# Clock_Flash.net
KiCad netlist of a schematic drawn in Altium Designer
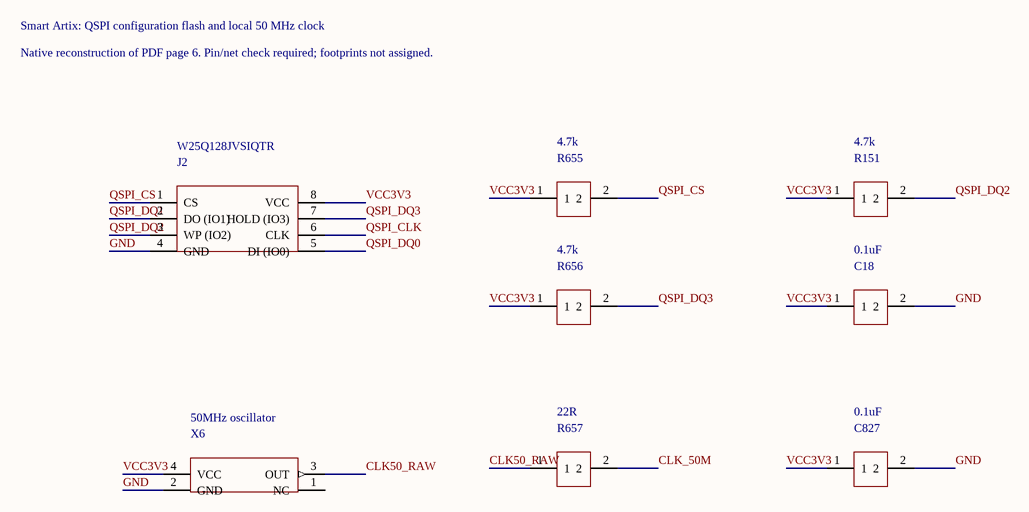
[diagram p0: Clock_Flash.SchDoc]

(export (version "E")
  (design (tool "Eeschema 10.0.6"))
  (components
    (comp (ref "C18")
      (value "0.1uF")
      (description "Reconstructed from Smart Artix reference PDF")
      (libsource (lib "*") (part "0.1uF"))
    )
    (comp (ref "C827")
      (value "0.1uF")
      (description "Reconstructed from Smart Artix reference PDF")
      (libsource (lib "*") (part "0.1uF"))
    )
    (comp (ref "J2")
      (value "W25Q128JVSIQTR")
      (description "Reconstructed from Smart Artix reference PDF")
      (libsource (lib "*") (part "W25Q128JVSIQTR"))
    )
    (comp (ref "R151")
      (value "4.7k")
      (description "Reconstructed from Smart Artix reference PDF")
      (libsource (lib "*") (part "4.7k"))
    )
    (comp (ref "R655")
      (value "4.7k")
      (description "Reconstructed from Smart Artix reference PDF")
      (libsource (lib "*") (part "4.7k"))
    )
    (comp (ref "R656")
      (value "4.7k")
      (description "Reconstructed from Smart Artix reference PDF")
      (libsource (lib "*") (part "4.7k"))
    )
    (comp (ref "R657")
      (value "22R")
      (description "Reconstructed from Smart Artix reference PDF")
      (libsource (lib "*") (part "22R"))
    )
    (comp (ref "X6")
      (value "50MHz oscillator")
      (description "Reconstructed from Smart Artix reference PDF")
      (libsource (lib "*") (part "50MHz oscillator"))
    )
  )
  (nets
    (net (code "1") (name "/CLK50_RAW") (class "Default")
      (node (ref "R657") (pin "1") (pinfunction "1_1") (pintype "passive"))
      (node (ref "X6") (pin "3") (pinfunction "OUT_3") (pintype "output"))
    )
    (net (code "2") (name "/CLK_50M") (class "Default")
      (node (ref "R657") (pin "2") (pinfunction "2_2") (pintype "passive"))
    )
    (net (code "3") (name "/GND") (class "Default")
      (node (ref "C18") (pin "2") (pinfunction "2_2") (pintype "passive"))
      (node (ref "C827") (pin "2") (pinfunction "2_2") (pintype "passive"))
      (node (ref "J2") (pin "4") (pinfunction "GND_4") (pintype "power_in"))
      (node (ref "X6") (pin "2") (pinfunction "GND_2") (pintype "power_in"))
    )
    (net (code "4") (name "/QSPI_CLK") (class "Default")
      (node (ref "J2") (pin "6") (pinfunction "CLK_6") (pintype "passive"))
    )
    (net (code "5") (name "/QSPI_CS") (class "Default")
      (node (ref "J2") (pin "1") (pinfunction "CS_1") (pintype "passive"))
      (node (ref "R655") (pin "2") (pinfunction "2_2") (pintype "passive"))
    )
    (net (code "6") (name "/QSPI_DQ0") (class "Default")
      (node (ref "J2") (pin "5") (pinfunction "DI_(IO0)_5") (pintype "passive"))
    )
    (net (code "7") (name "/QSPI_DQ1") (class "Default")
      (node (ref "J2") (pin "2") (pinfunction "DO_(IO1)_2") (pintype "passive"))
    )
    (net (code "8") (name "/QSPI_DQ2") (class "Default")
      (node (ref "J2") (pin "3") (pinfunction "WP_(IO2)_3") (pintype "passive"))
      (node (ref "R151") (pin "2") (pinfunction "2_2") (pintype "passive"))
    )
    (net (code "9") (name "/QSPI_DQ3") (class "Default")
      (node (ref "J2") (pin "7") (pinfunction "HOLD_(IO3)_7") (pintype "passive"))
      (node (ref "R656") (pin "2") (pinfunction "2_2") (pintype "passive"))
    )
    (net (code "10") (name "/VCC3V3") (class "Default")
      (node (ref "C18") (pin "1") (pinfunction "1_1") (pintype "passive"))
      (node (ref "C827") (pin "1") (pinfunction "1_1") (pintype "passive"))
      (node (ref "J2") (pin "8") (pinfunction "VCC_8") (pintype "power_in"))
      (node (ref "R151") (pin "1") (pinfunction "1_1") (pintype "passive"))
      (node (ref "R655") (pin "1") (pinfunction "1_1") (pintype "passive"))
      (node (ref "R656") (pin "1") (pinfunction "1_1") (pintype "passive"))
      (node (ref "X6") (pin "4") (pinfunction "VCC_4") (pintype "power_in"))
    )
    (net (code "11") (name "unconnected-(X6-NC-Pad1)") (class "Default")
      (node (ref "X6") (pin "1") (pinfunction "NC_1") (pintype "passive"))
    )
  )
)
